# G4_TechWatch-BASIC.net
KiCad netlist of a schematic drawn in EAGLE
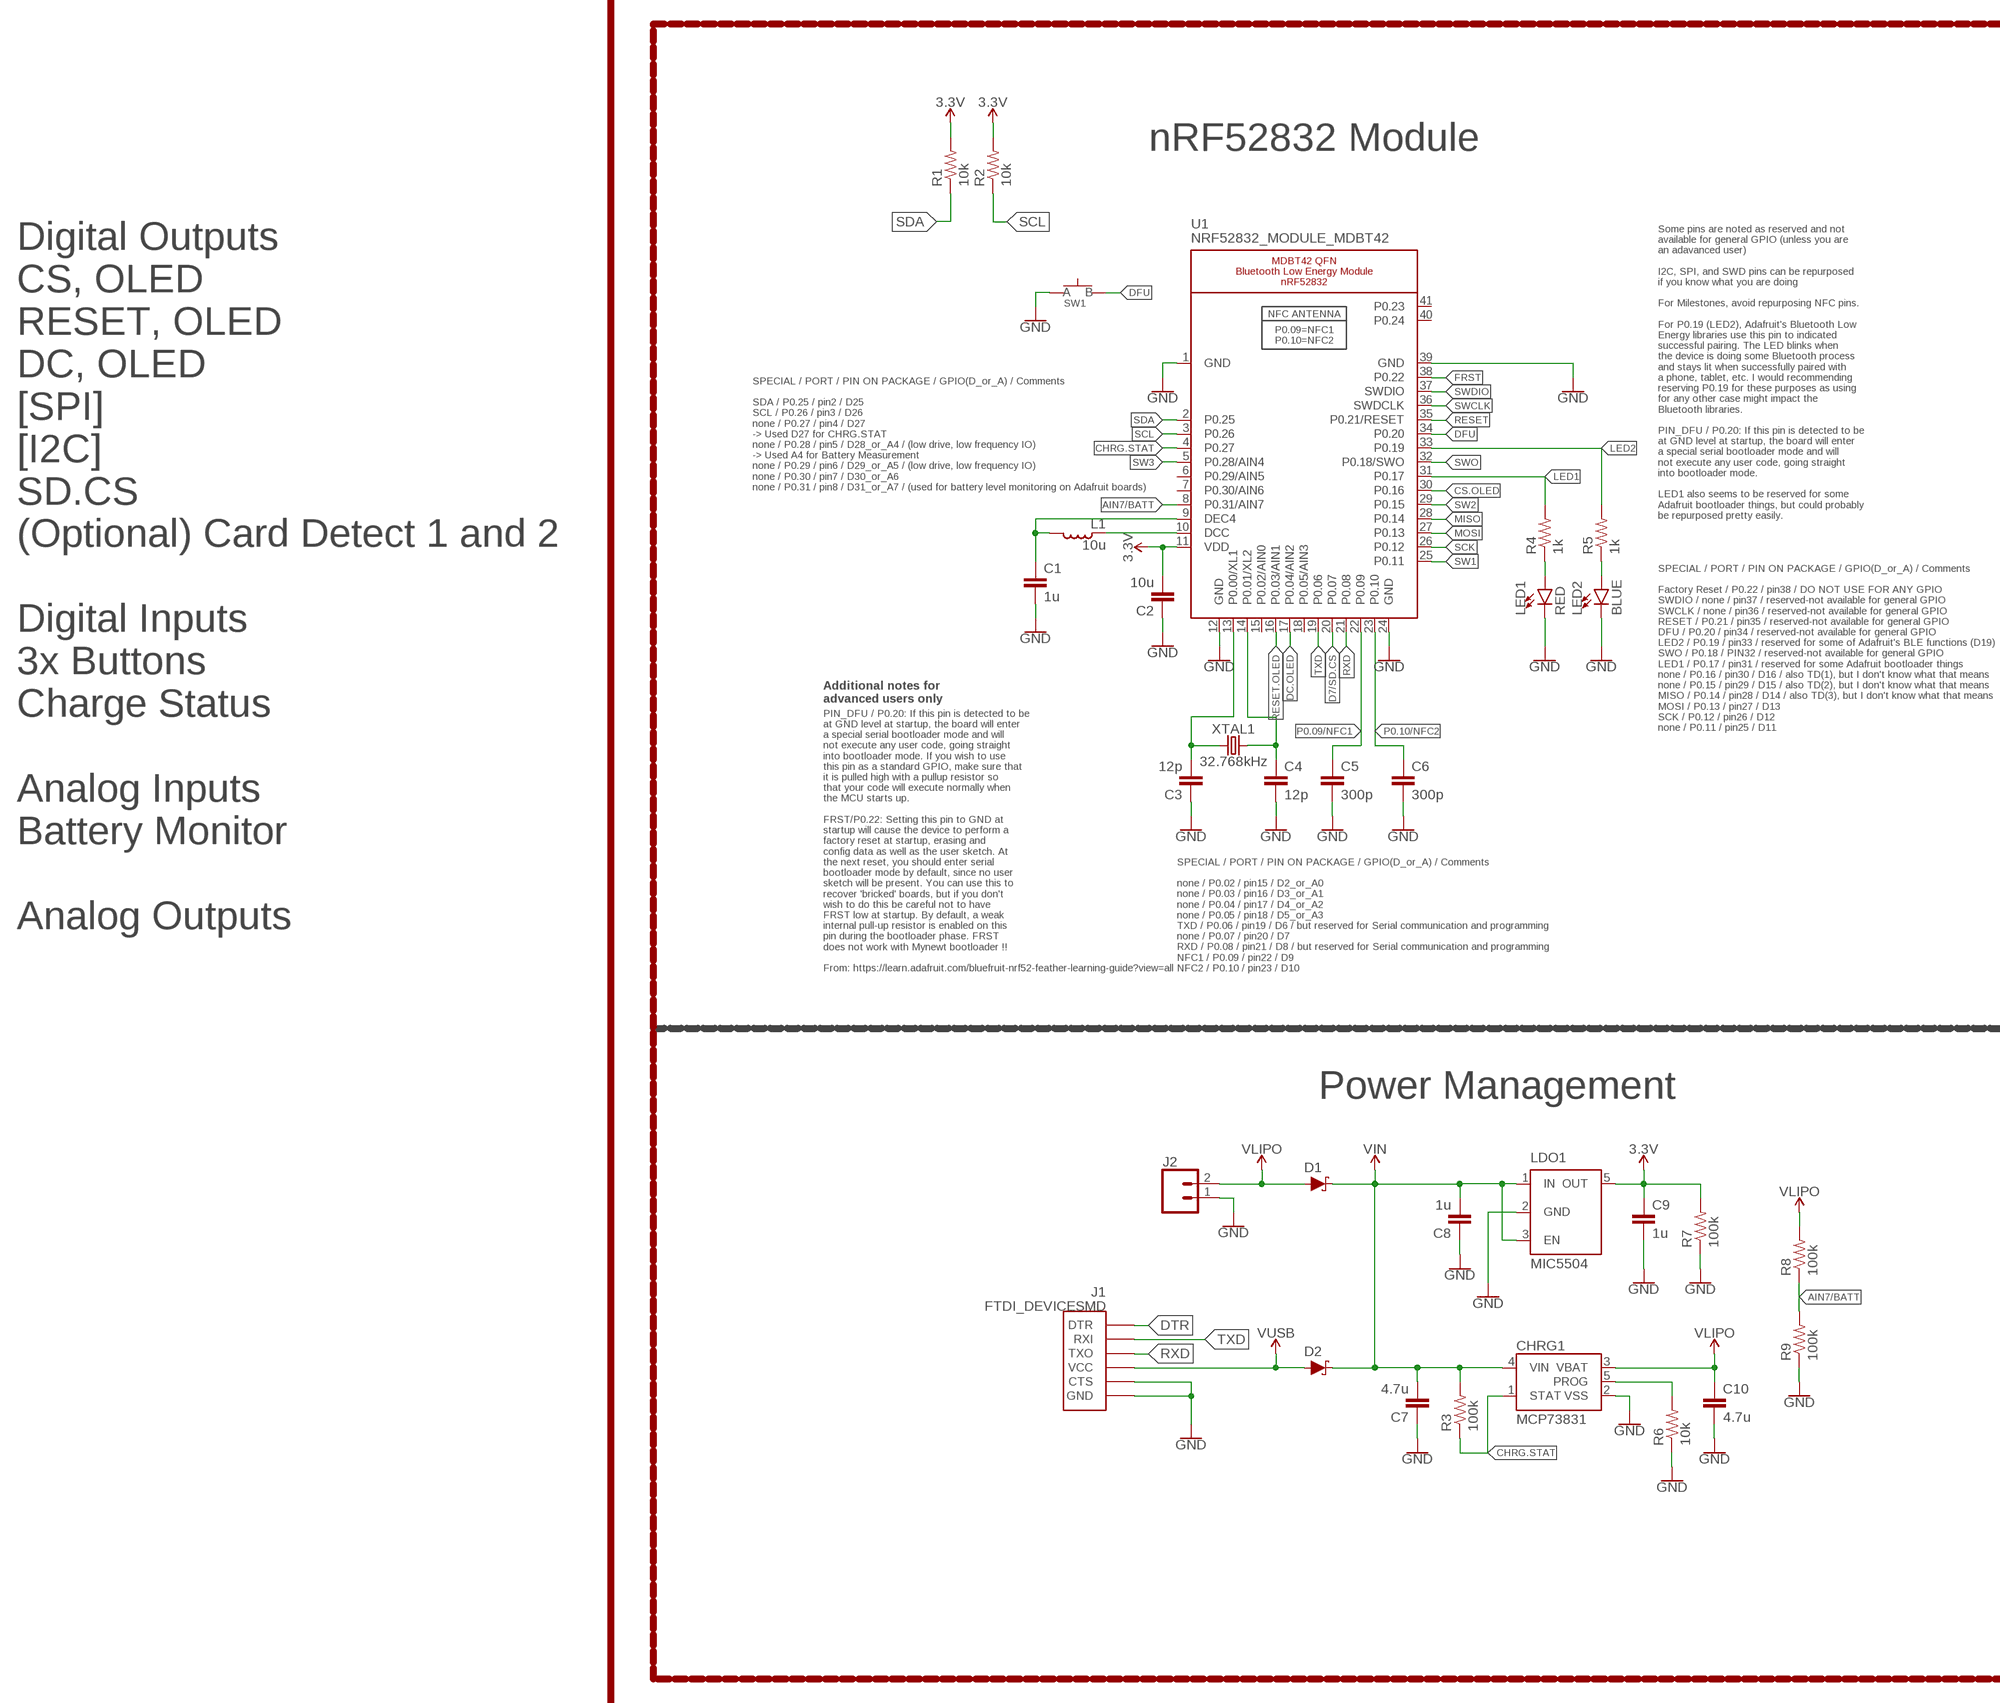
[diagram p0: schematic, sheet 1, part 1 of 2]
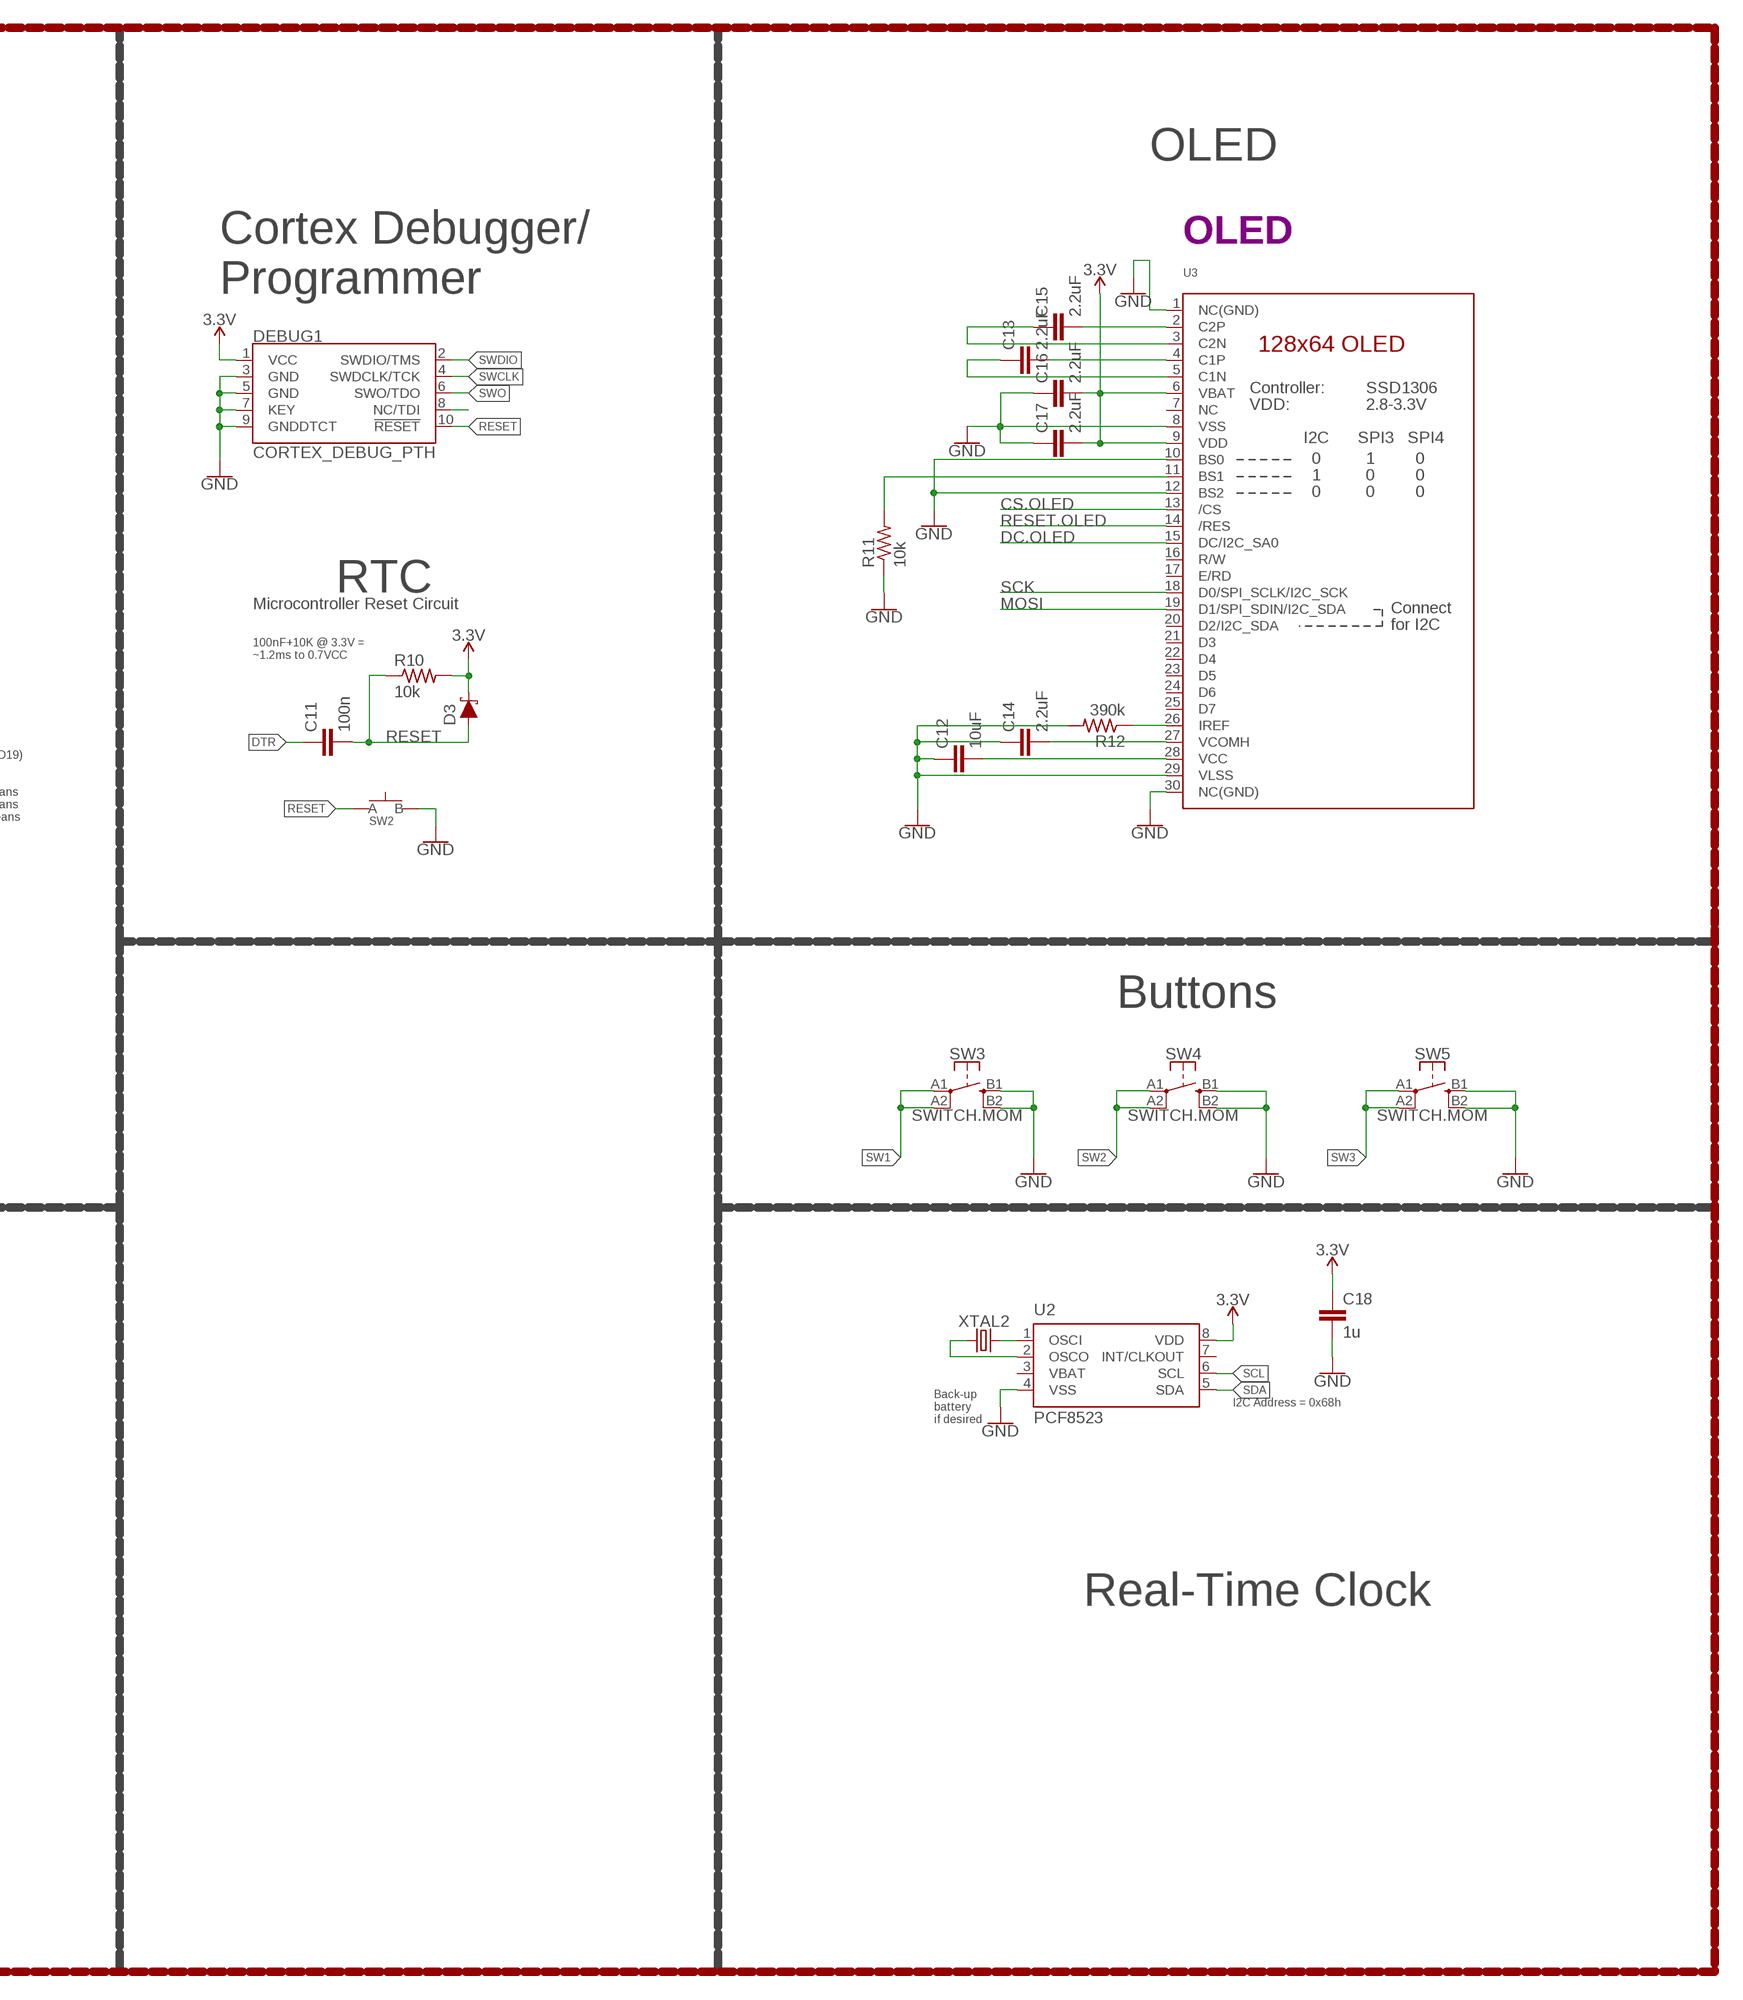
[diagram p1: schematic, sheet 1, part 2 of 2]

(export (version "E")
  (design (tool "Eeschema 10.0.6"))
  (components
    (comp (ref "C1")
      (value "1u")
      (footprint "eagle-import:C0603")
      (libsource (lib "eagle-import") (part "CAPACITOR0603"))
    )
    (comp (ref "C2")
      (value "10u")
      (footprint "eagle-import:C0805")
      (libsource (lib "eagle-import") (part "CAPACITOR0805"))
    )
    (comp (ref "C3")
      (value "12p")
      (footprint "eagle-import:C0603")
      (libsource (lib "eagle-import") (part "CAPACITOR0603"))
    )
    (comp (ref "C4")
      (value "12p")
      (footprint "eagle-import:C0603")
      (libsource (lib "eagle-import") (part "CAPACITOR0603"))
    )
    (comp (ref "C5")
      (value "300p")
      (footprint "eagle-import:C0603")
      (libsource (lib "eagle-import") (part "CAPACITOR0603"))
    )
    (comp (ref "C6")
      (value "300p")
      (footprint "eagle-import:C0603")
      (libsource (lib "eagle-import") (part "CAPACITOR0603"))
    )
    (comp (ref "C7")
      (value "4.7u")
      (footprint "eagle-import:C0603")
      (libsource (lib "eagle-import") (part "CAPACITOR0603"))
    )
    (comp (ref "C8")
      (value "1u")
      (footprint "eagle-import:C0603")
      (libsource (lib "eagle-import") (part "CAPACITOR0603"))
    )
    (comp (ref "C9")
      (value "1u")
      (footprint "eagle-import:C0603")
      (libsource (lib "eagle-import") (part "CAPACITOR0603"))
    )
    (comp (ref "C10")
      (value "4.7u")
      (footprint "eagle-import:C0603")
      (libsource (lib "eagle-import") (part "CAPACITOR0603"))
    )
    (comp (ref "C11")
      (value "100n")
      (footprint "eagle-import:C0603")
      (libsource (lib "eagle-import") (part "CAPACITOR0603"))
    )
    (comp (ref "C12")
      (value "10uF")
      (footprint "eagle-import:C0603")
      (libsource (lib "eagle-import") (part "CAPACITOR0603"))
    )
    (comp (ref "C13")
      (value "2.2uF")
      (footprint "eagle-import:C0402")
      (libsource (lib "eagle-import") (part "CAPACITOR0402"))
    )
    (comp (ref "C14")
      (value "2.2uF")
      (footprint "eagle-import:C0402")
      (libsource (lib "eagle-import") (part "CAPACITOR0402"))
    )
    (comp (ref "C15")
      (value "2.2uF")
      (footprint "eagle-import:C0402")
      (libsource (lib "eagle-import") (part "CAPACITOR0402"))
    )
    (comp (ref "C16")
      (value "2.2uF")
      (footprint "eagle-import:C0402")
      (libsource (lib "eagle-import") (part "CAPACITOR0402"))
    )
    (comp (ref "C17")
      (value "2.2uF")
      (footprint "eagle-import:C0402")
      (libsource (lib "eagle-import") (part "CAPACITOR0402"))
    )
    (comp (ref "C18")
      (value "1u")
      (footprint "eagle-import:C0603")
      (libsource (lib "eagle-import") (part "CAPACITOR0603"))
    )
    (comp (ref "CHRG1")
      (value "MCP73831")
      (footprint "eagle-import:SOT23-5")
      (libsource (lib "eagle-import") (part "MCP73831"))
    )
    (comp (ref "D1")
      (value "SCHOTTKY-USC")
      (footprint "eagle-import:USC")
      (libsource (lib "eagle-import") (part "SCHOTTKY-USC"))
    )
    (comp (ref "D2")
      (value "SCHOTTKY-USC")
      (footprint "eagle-import:USC")
      (libsource (lib "eagle-import") (part "SCHOTTKY-USC"))
    )
    (comp (ref "D3")
      (value "SCHOTTKY-USC")
      (footprint "eagle-import:USC")
      (libsource (lib "eagle-import") (part "SCHOTTKY-USC"))
    )
    (comp (ref "DEBUG1")
      (value "CORTEX_DEBUG_PTH")
      (footprint "eagle-import:2X5-PTH-1.27MM")
      (libsource (lib "eagle-import") (part "CORTEX_DEBUG_PTH"))
    )
    (comp (ref "J1")
      (value "FTDI_DEVICESMD")
      (footprint "eagle-import:FTDI-SMD")
      (libsource (lib "eagle-import") (part "FTDI_DEVICESMD"))
    )
    (comp (ref "J2")
      (value "CONN_02")
      (footprint "eagle-import:1X02")
      (libsource (lib "eagle-import") (part "CONN_02"))
    )
    (comp (ref "L1")
      (value "10u")
      (footprint "eagle-import:L0603")
      (libsource (lib "eagle-import") (part "INDUCTOR0603"))
    )
    (comp (ref "LDO1")
      (value "MIC5504")
      (footprint "eagle-import:SOT23-5")
      (libsource (lib "eagle-import") (part "MIC5504"))
    )
    (comp (ref "LED1")
      (value "RED")
      (footprint "eagle-import:LED-0603")
      (libsource (lib "eagle-import") (part "LED0603"))
    )
    (comp (ref "LED2")
      (value "BLUE")
      (footprint "eagle-import:LED-0603")
      (libsource (lib "eagle-import") (part "LED0603"))
    )
    (comp (ref "R1")
      (value "10k")
      (footprint "eagle-import:R0603")
      (libsource (lib "eagle-import") (part "RESISTOR0603"))
    )
    (comp (ref "R2")
      (value "10k")
      (footprint "eagle-import:R0603")
      (libsource (lib "eagle-import") (part "RESISTOR0603"))
    )
    (comp (ref "R3")
      (value "100k")
      (footprint "eagle-import:R0603")
      (libsource (lib "eagle-import") (part "RESISTOR0603"))
    )
    (comp (ref "R4")
      (value "1k")
      (footprint "eagle-import:R0603")
      (libsource (lib "eagle-import") (part "RESISTOR0603"))
    )
    (comp (ref "R5")
      (value "1k")
      (footprint "eagle-import:R0603")
      (libsource (lib "eagle-import") (part "RESISTOR0603"))
    )
    (comp (ref "R6")
      (value "10k")
      (footprint "eagle-import:R0603")
      (libsource (lib "eagle-import") (part "RESISTOR0603"))
    )
    (comp (ref "R7")
      (value "100k")
      (footprint "eagle-import:R0603")
      (libsource (lib "eagle-import") (part "RESISTOR0603"))
    )
    (comp (ref "R8")
      (value "100k")
      (footprint "eagle-import:R0603")
      (libsource (lib "eagle-import") (part "RESISTOR0603"))
    )
    (comp (ref "R9")
      (value "100k")
      (footprint "eagle-import:R0603")
      (libsource (lib "eagle-import") (part "RESISTOR0603"))
    )
    (comp (ref "R10")
      (value "10k")
      (footprint "eagle-import:R0603")
      (libsource (lib "eagle-import") (part "RESISTOR0603"))
    )
    (comp (ref "R11")
      (value "10k")
      (footprint "eagle-import:R0603")
      (libsource (lib "eagle-import") (part "RESISTOR0603"))
    )
    (comp (ref "R12")
      (value "390k")
      (footprint "eagle-import:R0603")
      (libsource (lib "eagle-import") (part "RESISTOR0603"))
    )
    (comp (ref "SW1")
      (value "SPST-PTS830GG140-COPY.1-3")
      (footprint "eagle-import:BUTTON-GULLWING")
      (libsource (lib "eagle-import") (part "SPST-PTS830GG140-COPY.1-3"))
    )
    (comp (ref "SW2")
      (value "SPST-PTS830GG140-COPY.1-3")
      (footprint "eagle-import:BUTTON-GULLWING")
      (libsource (lib "eagle-import") (part "SPST-PTS830GG140-COPY.1-3"))
    )
    (comp (ref "SW3")
      (value "SWITCH.MOM")
      (footprint "eagle-import:TACTILE_SWITCH_SMD_6.2MM_TALL")
      (libsource (lib "eagle-import") (part "SWITCH.MOM"))
    )
    (comp (ref "SW4")
      (value "SWITCH.MOM")
      (footprint "eagle-import:TACTILE_SWITCH_SMD_6.2MM_TALL")
      (libsource (lib "eagle-import") (part "SWITCH.MOM"))
    )
    (comp (ref "SW5")
      (value "SWITCH.MOM")
      (footprint "eagle-import:TACTILE_SWITCH_SMD_6.2MM_TALL")
      (libsource (lib "eagle-import") (part "SWITCH.MOM"))
    )
    (comp (ref "U1")
      (value "NRF52832_MODULE_MDBT42")
      (footprint "eagle-import:BLE_MODULE_RAYTAC_MDBT42")
      (libsource (lib "eagle-import") (part "NRF52832_MODULE_MDBT42"))
    )
    (comp (ref "U2")
      (value "PCF8523")
      (footprint "eagle-import:SO8")
      (libsource (lib "eagle-import") (part "PCF8523"))
    )
    (comp (ref "U3")
      (value "DISP_OLED_UG-2864HSWEG01-NO-WRAPAROUND")
      (footprint "eagle-import:UG-2864HSWEG01_0.96IN_NO-WRAPAROUND")
      (libsource (lib "eagle-import") (part "DISP_OLED_UG-2864HSWEG01-NO-WRAPAROUND"))
    )
    (comp (ref "XTAL1")
      (value "32.768kHz")
      (footprint "eagle-import:2-SMD.NOLEAD.2.0MMTO1.2MM")
      (libsource (lib "eagle-import") (part "CRYSTALECS-.327-12.5-12-C-TR"))
    )
    (comp (ref "XTAL2")
      (value "32.7680kHz")
      (footprint "eagle-import:2-SMD.NOLEAD.2.0MMTO1.2MM")
      (fields (field (name "FREQ") "32.7680KHZ"))
      (libsource (lib "eagle-import") (part "CRYSTALECS-.327-12.5-12-C-TR"))
    )
  )
  (nets
    (net (code "1") (name "/VBAT") (class "Default")
      (node (ref "U2") (pin "3") (pinfunction "VBAT_3") (pintype "power_in"))
    )
    (net (code "2") (name "3.3V") (class "Default")
      (node (ref "C16") (pin "2") (pinfunction "2_2") (pintype "passive"))
      (node (ref "C17") (pin "2") (pinfunction "2_2") (pintype "passive"))
      (node (ref "C18") (pin "1") (pinfunction "1_1") (pintype "passive"))
      (node (ref "C2") (pin "2") (pinfunction "2_2") (pintype "passive"))
      (node (ref "C9") (pin "1") (pinfunction "1_1") (pintype "passive"))
      (node (ref "D3") (pin "-") (pinfunction "C_-") (pintype "passive"))
      (node (ref "DEBUG1") (pin "1") (pinfunction "VCC_1") (pintype "bidirectional"))
      (node (ref "LDO1") (pin "5") (pinfunction "OUT_5") (pintype "bidirectional"))
      (node (ref "R1") (pin "2") (pinfunction "2_2") (pintype "passive"))
      (node (ref "R10") (pin "2") (pinfunction "2_2") (pintype "passive"))
      (node (ref "R2") (pin "2") (pinfunction "2_2") (pintype "passive"))
      (node (ref "R7") (pin "2") (pinfunction "2_2") (pintype "passive"))
      (node (ref "U1") (pin "11") (pinfunction "VDD_11") (pintype "bidirectional"))
      (node (ref "U2") (pin "8") (pinfunction "VDD_8") (pintype "power_in"))
      (node (ref "U3") (pin "6") (pinfunction "VBAT_6") (pintype "input"))
      (node (ref "U3") (pin "9") (pinfunction "VDD_9") (pintype "power_in"))
    )
    (net (code "3") (name "AIN7{slash}BATT") (class "Default")
      (node (ref "R8") (pin "1") (pinfunction "1_1") (pintype "passive"))
      (node (ref "R9") (pin "2") (pinfunction "2_2") (pintype "passive"))
      (node (ref "U1") (pin "8") (pinfunction "P0.31/AIN7_8") (pintype "bidirectional"))
    )
    (net (code "4") (name "CHRG.STAT") (class "Default")
      (node (ref "CHRG1") (pin "1") (pinfunction "STAT_1") (pintype "output"))
      (node (ref "R3") (pin "1") (pinfunction "1_1") (pintype "passive"))
      (node (ref "U1") (pin "4") (pinfunction "P0.27_4") (pintype "bidirectional"))
    )
    (net (code "5") (name "CS.OLED") (class "Default")
      (node (ref "U1") (pin "30") (pinfunction "P0.16_30") (pintype "bidirectional"))
      (node (ref "U3") (pin "13") (pinfunction "/CS_13") (pintype "input"))
    )
    (net (code "6") (name "D7{slash}SD.CS") (class "Default")
      (node (ref "U1") (pin "20") (pinfunction "P0.07_20") (pintype "bidirectional"))
    )
    (net (code "7") (name "DC.OLED") (class "Default")
      (node (ref "U1") (pin "17") (pinfunction "P0.04/AIN2_17") (pintype "bidirectional"))
      (node (ref "U3") (pin "15") (pinfunction "DC/I2C_SA0_15") (pintype "input"))
    )
    (net (code "8") (name "DFU") (class "Default")
      (node (ref "SW1") (pin "3") (pinfunction "B_3") (pintype "bidirectional"))
      (node (ref "U1") (pin "34") (pinfunction "P0.20_34") (pintype "bidirectional"))
    )
    (net (code "9") (name "DTR") (class "Default")
      (node (ref "C11") (pin "1") (pinfunction "1_1") (pintype "passive"))
      (node (ref "J1") (pin "DTR") (pinfunction "DTR_DTR") (pintype "bidirectional"))
    )
    (net (code "10") (name "FRST") (class "Default")
      (node (ref "U1") (pin "38") (pinfunction "P0.22_38") (pintype "bidirectional"))
    )
    (net (code "11") (name "GND") (class "Default")
      (node (ref "C1") (pin "2") (pinfunction "2_2") (pintype "passive"))
      (node (ref "C10") (pin "2") (pinfunction "2_2") (pintype "passive"))
      (node (ref "C12") (pin "1") (pinfunction "1_1") (pintype "passive"))
      (node (ref "C14") (pin "1") (pinfunction "1_1") (pintype "passive"))
      (node (ref "C16") (pin "1") (pinfunction "1_1") (pintype "passive"))
      (node (ref "C17") (pin "1") (pinfunction "1_1") (pintype "passive"))
      (node (ref "C18") (pin "2") (pinfunction "2_2") (pintype "passive"))
      (node (ref "C2") (pin "1") (pinfunction "1_1") (pintype "passive"))
      (node (ref "C3") (pin "1") (pinfunction "1_1") (pintype "passive"))
      (node (ref "C4") (pin "2") (pinfunction "2_2") (pintype "passive"))
      (node (ref "C5") (pin "2") (pinfunction "2_2") (pintype "passive"))
      (node (ref "C6") (pin "2") (pinfunction "2_2") (pintype "passive"))
      (node (ref "C7") (pin "1") (pinfunction "1_1") (pintype "passive"))
      (node (ref "C8") (pin "1") (pinfunction "1_1") (pintype "passive"))
      (node (ref "C9") (pin "2") (pinfunction "2_2") (pintype "passive"))
      (node (ref "CHRG1") (pin "2") (pinfunction "VSS_2") (pintype "power_in"))
      (node (ref "DEBUG1") (pin "3") (pinfunction "GND_3") (pintype "bidirectional"))
      (node (ref "DEBUG1") (pin "5") (pinfunction "GND_5") (pintype "bidirectional"))
      (node (ref "DEBUG1") (pin "7") (pinfunction "KEY_7") (pintype "bidirectional"))
      (node (ref "DEBUG1") (pin "9") (pinfunction "GNDDTCT_9") (pintype "bidirectional"))
      (node (ref "J1") (pin "CTS") (pinfunction "CTS_CTS") (pintype "bidirectional"))
      (node (ref "J1") (pin "GND") (pinfunction "GND_GND") (pintype "bidirectional"))
      (node (ref "J2") (pin "1") (pinfunction "1_1") (pintype "passive"))
      (node (ref "LDO1") (pin "2") (pinfunction "GND_2") (pintype "bidirectional"))
      (node (ref "LED1") (pin "C") (pinfunction "C_C") (pintype "passive"))
      (node (ref "LED2") (pin "C") (pinfunction "C_C") (pintype "passive"))
      (node (ref "R11") (pin "1") (pinfunction "1_1") (pintype "passive"))
      (node (ref "R12") (pin "2") (pinfunction "2_2") (pintype "passive"))
      (node (ref "R6") (pin "1") (pinfunction "1_1") (pintype "passive"))
      (node (ref "R7") (pin "1") (pinfunction "1_1") (pintype "passive"))
      (node (ref "R9") (pin "1") (pinfunction "1_1") (pintype "passive"))
      (node (ref "SW1") (pin "1") (pinfunction "A_1") (pintype "bidirectional"))
      (node (ref "SW2") (pin "3") (pinfunction "B_3") (pintype "bidirectional"))
      (node (ref "SW3") (pin "B1") (pinfunction "3_B1") (pintype "passive"))
      (node (ref "SW3") (pin "B2") (pinfunction "4_B2") (pintype "passive"))
      (node (ref "SW4") (pin "B1") (pinfunction "3_B1") (pintype "passive"))
      (node (ref "SW4") (pin "B2") (pinfunction "4_B2") (pintype "passive"))
      (node (ref "SW5") (pin "B1") (pinfunction "3_B1") (pintype "passive"))
      (node (ref "SW5") (pin "B2") (pinfunction "4_B2") (pintype "passive"))
      (node (ref "U1") (pin "1") (pinfunction "GND_1") (pintype "bidirectional"))
      (node (ref "U1") (pin "12") (pinfunction "GND_12") (pintype "bidirectional"))
      (node (ref "U1") (pin "24") (pinfunction "GND_24") (pintype "bidirectional"))
      (node (ref "U1") (pin "39") (pinfunction "GND_39") (pintype "bidirectional"))
      (node (ref "U2") (pin "4") (pinfunction "VSS_4") (pintype "power_in"))
      (node (ref "U3") (pin "1") (pinfunction "NC(GND)_1") (pintype "input"))
      (node (ref "U3") (pin "10") (pinfunction "BS0_10") (pintype "input"))
      (node (ref "U3") (pin "12") (pinfunction "BS2_12") (pintype "input"))
      (node (ref "U3") (pin "29") (pinfunction "VLSS_29") (pintype "power_in"))
      (node (ref "U3") (pin "30") (pinfunction "NC(GND)_30") (pintype "input"))
      (node (ref "U3") (pin "8") (pinfunction "VSS_8") (pintype "power_in"))
    )
    (net (code "12") (name "LED1") (class "Default")
      (node (ref "R4") (pin "2") (pinfunction "2_2") (pintype "passive"))
      (node (ref "U1") (pin "31") (pinfunction "P0.17_31") (pintype "bidirectional"))
    )
    (net (code "13") (name "LED2") (class "Default")
      (node (ref "R5") (pin "2") (pinfunction "2_2") (pintype "passive"))
      (node (ref "U1") (pin "33") (pinfunction "P0.19_33") (pintype "bidirectional"))
    )
    (net (code "14") (name "MISO") (class "Default")
      (node (ref "U1") (pin "28") (pinfunction "P0.14_28") (pintype "bidirectional"))
    )
    (net (code "15") (name "MOSI") (class "Default")
      (node (ref "U1") (pin "27") (pinfunction "P0.13_27") (pintype "bidirectional"))
      (node (ref "U3") (pin "19") (pinfunction "D1/SPI_SDIN/I2C_SDA_19") (pintype "bidirectional"))
    )
    (net (code "16") (name "Net-(CHRG1-PROG)") (class "Default")
      (node (ref "CHRG1") (pin "5") (pinfunction "PROG_5") (pintype "input"))
      (node (ref "R6") (pin "2") (pinfunction "2_2") (pintype "passive"))
    )
    (net (code "17") (name "Net-(LED1-PadA)") (class "Default")
      (node (ref "LED1") (pin "A") (pinfunction "A_A") (pintype "passive"))
      (node (ref "R4") (pin "1") (pinfunction "1_1") (pintype "passive"))
    )
    (net (code "18") (name "Net-(LED2-PadA)") (class "Default")
      (node (ref "LED2") (pin "A") (pinfunction "A_A") (pintype "passive"))
      (node (ref "R5") (pin "1") (pinfunction "1_1") (pintype "passive"))
    )
    (net (code "19") (name "Net-(U1-DCC)") (class "Default")
      (node (ref "L1") (pin "1") (pinfunction "1_1") (pintype "passive"))
      (node (ref "U1") (pin "10") (pinfunction "DCC_10") (pintype "bidirectional"))
    )
    (net (code "20") (name "Net-(U1-DEC4)") (class "Default")
      (node (ref "C1") (pin "1") (pinfunction "1_1") (pintype "passive"))
      (node (ref "L1") (pin "2") (pinfunction "2_2") (pintype "passive"))
      (node (ref "U1") (pin "9") (pinfunction "DEC4_9") (pintype "bidirectional"))
    )
    (net (code "21") (name "Net-(U1-P0.00{slash}XL1)") (class "Default")
      (node (ref "C3") (pin "2") (pinfunction "2_2") (pintype "passive"))
      (node (ref "U1") (pin "13") (pinfunction "P0.00/XL1_13") (pintype "bidirectional"))
      (node (ref "XTAL1") (pin "P$1") (pinfunction "1_P$1") (pintype "passive"))
    )
    (net (code "22") (name "Net-(U1-P0.01{slash}XL2)") (class "Default")
      (node (ref "C4") (pin "1") (pinfunction "1_1") (pintype "passive"))
      (node (ref "U1") (pin "14") (pinfunction "P0.01/XL2_14") (pintype "bidirectional"))
      (node (ref "XTAL1") (pin "P$2") (pinfunction "2_P$2") (pintype "passive"))
    )
    (net (code "23") (name "Net-(U2-OSCI)") (class "Default")
      (node (ref "U2") (pin "1") (pinfunction "OSCI_1") (pintype "bidirectional"))
      (node (ref "XTAL2") (pin "P$2") (pinfunction "2_P$2") (pintype "passive"))
    )
    (net (code "24") (name "Net-(U2-OSCO)") (class "Default")
      (node (ref "U2") (pin "2") (pinfunction "OSCO_2") (pintype "bidirectional"))
      (node (ref "XTAL2") (pin "P$1") (pinfunction "1_P$1") (pintype "passive"))
    )
    (net (code "25") (name "Net-(U3-BS1)") (class "Default")
      (node (ref "R11") (pin "2") (pinfunction "2_2") (pintype "passive"))
      (node (ref "U3") (pin "11") (pinfunction "BS1_11") (pintype "input"))
    )
    (net (code "26") (name "Net-(U3-C1N)") (class "Default")
      (node (ref "C13") (pin "1") (pinfunction "1_1") (pintype "passive"))
      (node (ref "U3") (pin "5") (pinfunction "C1N_5") (pintype "input"))
    )
    (net (code "27") (name "Net-(U3-C1P)") (class "Default")
      (node (ref "C13") (pin "2") (pinfunction "2_2") (pintype "passive"))
      (node (ref "U3") (pin "4") (pinfunction "C1P_4") (pintype "input"))
    )
    (net (code "28") (name "Net-(U3-C2N)") (class "Default")
      (node (ref "C15") (pin "1") (pinfunction "1_1") (pintype "passive"))
      (node (ref "U3") (pin "3") (pinfunction "C2N_3") (pintype "input"))
    )
    (net (code "29") (name "Net-(U3-C2P)") (class "Default")
      (node (ref "C15") (pin "2") (pinfunction "2_2") (pintype "passive"))
      (node (ref "U3") (pin "2") (pinfunction "C2P_2") (pintype "input"))
    )
    (net (code "30") (name "Net-(U3-IREF)") (class "Default")
      (node (ref "R12") (pin "1") (pinfunction "1_1") (pintype "passive"))
      (node (ref "U3") (pin "26") (pinfunction "IREF_26") (pintype "input"))
    )
    (net (code "31") (name "Net-(U3-VCC)") (class "Default")
      (node (ref "C12") (pin "2") (pinfunction "2_2") (pintype "passive"))
      (node (ref "U3") (pin "28") (pinfunction "VCC_28") (pintype "power_in"))
    )
    (net (code "32") (name "Net-(U3-VCOMH)") (class "Default")
      (node (ref "C14") (pin "2") (pinfunction "2_2") (pintype "passive"))
      (node (ref "U3") (pin "27") (pinfunction "VCOMH_27") (pintype "output"))
    )
    (net (code "33") (name "P0.09{slash}NFC1") (class "Default")
      (node (ref "C5") (pin "1") (pinfunction "1_1") (pintype "passive"))
      (node (ref "U1") (pin "22") (pinfunction "P0.09_22") (pintype "bidirectional"))
    )
    (net (code "34") (name "P0.10{slash}NFC2") (class "Default")
      (node (ref "C6") (pin "1") (pinfunction "1_1") (pintype "passive"))
      (node (ref "U1") (pin "23") (pinfunction "P0.10_23") (pintype "bidirectional"))
    )
    (net (code "35") (name "RESET") (class "Default")
      (node (ref "C11") (pin "2") (pinfunction "2_2") (pintype "passive"))
      (node (ref "D3") (pin "+") (pinfunction "A_+") (pintype "passive"))
      (node (ref "DEBUG1") (pin "10") (pinfunction "~{RESET}_10") (pintype "bidirectional"))
      (node (ref "R10") (pin "1") (pinfunction "1_1") (pintype "passive"))
      (node (ref "SW2") (pin "1") (pinfunction "A_1") (pintype "bidirectional"))
      (node (ref "U1") (pin "35") (pinfunction "P0.21/RESET_35") (pintype "bidirectional"))
    )
    (net (code "36") (name "RESET.OLED") (class "Default")
      (node (ref "U1") (pin "16") (pinfunction "P0.03/AIN1_16") (pintype "bidirectional"))
      (node (ref "U3") (pin "14") (pinfunction "/RES_14") (pintype "input"))
    )
    (net (code "37") (name "RXD") (class "Default")
      (node (ref "J1") (pin "TXO") (pinfunction "TXO_TXO") (pintype "bidirectional"))
      (node (ref "U1") (pin "21") (pinfunction "P0.08_21") (pintype "bidirectional"))
    )
    (net (code "38") (name "SCK") (class "Default")
      (node (ref "U1") (pin "26") (pinfunction "P0.12_26") (pintype "bidirectional"))
      (node (ref "U3") (pin "18") (pinfunction "D0/SPI_SCLK/I2C_SCK_18") (pintype "bidirectional"))
    )
    (net (code "39") (name "SCL") (class "Default")
      (node (ref "R2") (pin "1") (pinfunction "1_1") (pintype "passive"))
      (node (ref "U1") (pin "3") (pinfunction "P0.26_3") (pintype "bidirectional"))
      (node (ref "U2") (pin "6") (pinfunction "SCL_6") (pintype "bidirectional"))
    )
    (net (code "40") (name "SDA") (class "Default")
      (node (ref "R1") (pin "1") (pinfunction "1_1") (pintype "passive"))
      (node (ref "U1") (pin "2") (pinfunction "P0.25_2") (pintype "bidirectional"))
      (node (ref "U2") (pin "5") (pinfunction "SDA_5") (pintype "bidirectional"))
    )
    (net (code "41") (name "SW1") (class "Default")
      (node (ref "SW3") (pin "A1") (pinfunction "1_A1") (pintype "passive"))
      (node (ref "SW3") (pin "A2") (pinfunction "2_A2") (pintype "passive"))
      (node (ref "U1") (pin "25") (pinfunction "P0.11_25") (pintype "bidirectional"))
    )
    (net (code "42") (name "SW2") (class "Default")
      (node (ref "SW4") (pin "A1") (pinfunction "1_A1") (pintype "passive"))
      (node (ref "SW4") (pin "A2") (pinfunction "2_A2") (pintype "passive"))
      (node (ref "U1") (pin "29") (pinfunction "P0.15_29") (pintype "bidirectional"))
    )
    (net (code "43") (name "SW3") (class "Default")
      (node (ref "SW5") (pin "A1") (pinfunction "1_A1") (pintype "passive"))
      (node (ref "SW5") (pin "A2") (pinfunction "2_A2") (pintype "passive"))
      (node (ref "U1") (pin "5") (pinfunction "P0.28/AIN4_5") (pintype "bidirectional"))
    )
    (net (code "44") (name "SWCLK") (class "Default")
      (node (ref "DEBUG1") (pin "4") (pinfunction "SWDCLK/TCK_4") (pintype "bidirectional"))
      (node (ref "U1") (pin "36") (pinfunction "SWDCLK_36") (pintype "bidirectional"))
    )
    (net (code "45") (name "SWDIO") (class "Default")
      (node (ref "DEBUG1") (pin "2") (pinfunction "SWDIO/TMS_2") (pintype "bidirectional"))
      (node (ref "U1") (pin "37") (pinfunction "SWDIO_37") (pintype "bidirectional"))
    )
    (net (code "46") (name "SWO") (class "Default")
      (node (ref "DEBUG1") (pin "6") (pinfunction "SWO/TDO_6") (pintype "bidirectional"))
      (node (ref "U1") (pin "32") (pinfunction "P0.18/SWO_32") (pintype "bidirectional"))
    )
    (net (code "47") (name "TXD") (class "Default")
      (node (ref "J1") (pin "RXI") (pinfunction "RXI_RXI") (pintype "bidirectional"))
      (node (ref "U1") (pin "19") (pinfunction "P0.06_19") (pintype "bidirectional"))
    )
    (net (code "48") (name "VIN") (class "Default")
      (node (ref "C7") (pin "2") (pinfunction "2_2") (pintype "passive"))
      (node (ref "C8") (pin "2") (pinfunction "2_2") (pintype "passive"))
      (node (ref "CHRG1") (pin "4") (pinfunction "VIN_4") (pintype "power_in"))
      (node (ref "D1") (pin "-") (pinfunction "C_-") (pintype "passive"))
      (node (ref "D2") (pin "-") (pinfunction "C_-") (pintype "passive"))
      (node (ref "LDO1") (pin "1") (pinfunction "IN_1") (pintype "bidirectional"))
      (node (ref "LDO1") (pin "3") (pinfunction "EN_3") (pintype "bidirectional"))
      (node (ref "R3") (pin "2") (pinfunction "2_2") (pintype "passive"))
    )
    (net (code "49") (name "VLIPO") (class "Default")
      (node (ref "C10") (pin "1") (pinfunction "1_1") (pintype "passive"))
      (node (ref "CHRG1") (pin "3") (pinfunction "VBAT_3") (pintype "power_in"))
      (node (ref "D1") (pin "+") (pinfunction "A_+") (pintype "passive"))
      (node (ref "J2") (pin "2") (pinfunction "2_2") (pintype "passive"))
      (node (ref "R8") (pin "2") (pinfunction "2_2") (pintype "passive"))
    )
    (net (code "50") (name "VUSB") (class "Default")
      (node (ref "D2") (pin "+") (pinfunction "A_+") (pintype "passive"))
      (node (ref "J1") (pin "VCC") (pinfunction "VCC_VCC") (pintype "bidirectional"))
    )
    (net (code "51") (name "unconnected-(DEBUG1-NC{slash}TDI-Pad8)") (class "Default")
      (node (ref "DEBUG1") (pin "8") (pinfunction "NC/TDI_8") (pintype "bidirectional"))
    )
    (net (code "52") (name "unconnected-(U1-P0.02{slash}AIN0-Pad15)") (class "Default")
      (node (ref "U1") (pin "15") (pinfunction "P0.02/AIN0_15") (pintype "bidirectional"))
    )
    (net (code "53") (name "unconnected-(U1-P0.05{slash}AIN3-Pad18)") (class "Default")
      (node (ref "U1") (pin "18") (pinfunction "P0.05/AIN3_18") (pintype "bidirectional"))
    )
    (net (code "54") (name "unconnected-(U1-P0.23-Pad41)") (class "Default")
      (node (ref "U1") (pin "41") (pinfunction "P0.23_41") (pintype "bidirectional"))
    )
    (net (code "55") (name "unconnected-(U1-P0.24-Pad40)") (class "Default")
      (node (ref "U1") (pin "40") (pinfunction "P0.24_40") (pintype "bidirectional"))
    )
    (net (code "56") (name "unconnected-(U1-P0.29{slash}AIN5-Pad6)") (class "Default")
      (node (ref "U1") (pin "6") (pinfunction "P0.29/AIN5_6") (pintype "bidirectional"))
    )
    (net (code "57") (name "unconnected-(U1-P0.30{slash}AIN6-Pad7)") (class "Default")
      (node (ref "U1") (pin "7") (pinfunction "P0.30/AIN6_7") (pintype "bidirectional"))
    )
    (net (code "58") (name "unconnected-(U2-INT{slash}CLKOUT-Pad7)") (class "Default")
      (node (ref "U2") (pin "7") (pinfunction "INT/CLKOUT_7") (pintype "bidirectional"))
    )
    (net (code "59") (name "unconnected-(U3-D2{slash}I2C_SDA-Pad20)") (class "Default")
      (node (ref "U3") (pin "20") (pinfunction "D2/I2C_SDA_20") (pintype "bidirectional"))
    )
    (net (code "60") (name "unconnected-(U3-D3-Pad21)") (class "Default")
      (node (ref "U3") (pin "21") (pinfunction "D3_21") (pintype "bidirectional"))
    )
    (net (code "61") (name "unconnected-(U3-D4-Pad22)") (class "Default")
      (node (ref "U3") (pin "22") (pinfunction "D4_22") (pintype "bidirectional"))
    )
    (net (code "62") (name "unconnected-(U3-D5-Pad23)") (class "Default")
      (node (ref "U3") (pin "23") (pinfunction "D5_23") (pintype "bidirectional"))
    )
    (net (code "63") (name "unconnected-(U3-D6-Pad24)") (class "Default")
      (node (ref "U3") (pin "24") (pinfunction "D6_24") (pintype "bidirectional"))
    )
    (net (code "64") (name "unconnected-(U3-D7-Pad25)") (class "Default")
      (node (ref "U3") (pin "25") (pinfunction "D7_25") (pintype "bidirectional"))
    )
    (net (code "65") (name "unconnected-(U3-E{slash}RD-Pad17)") (class "Default")
      (node (ref "U3") (pin "17") (pinfunction "E/RD_17") (pintype "input"))
    )
    (net (code "66") (name "unconnected-(U3-NC-Pad7)") (class "Default")
      (node (ref "U3") (pin "7") (pinfunction "NC_7") (pintype "no_connect"))
    )
    (net (code "67") (name "unconnected-(U3-R{slash}W-Pad16)") (class "Default")
      (node (ref "U3") (pin "16") (pinfunction "R/W_16") (pintype "input"))
    )
  )
)
